# TarjetaModulo.net
KiCad netlist of a schematic drawn in Altium Designer
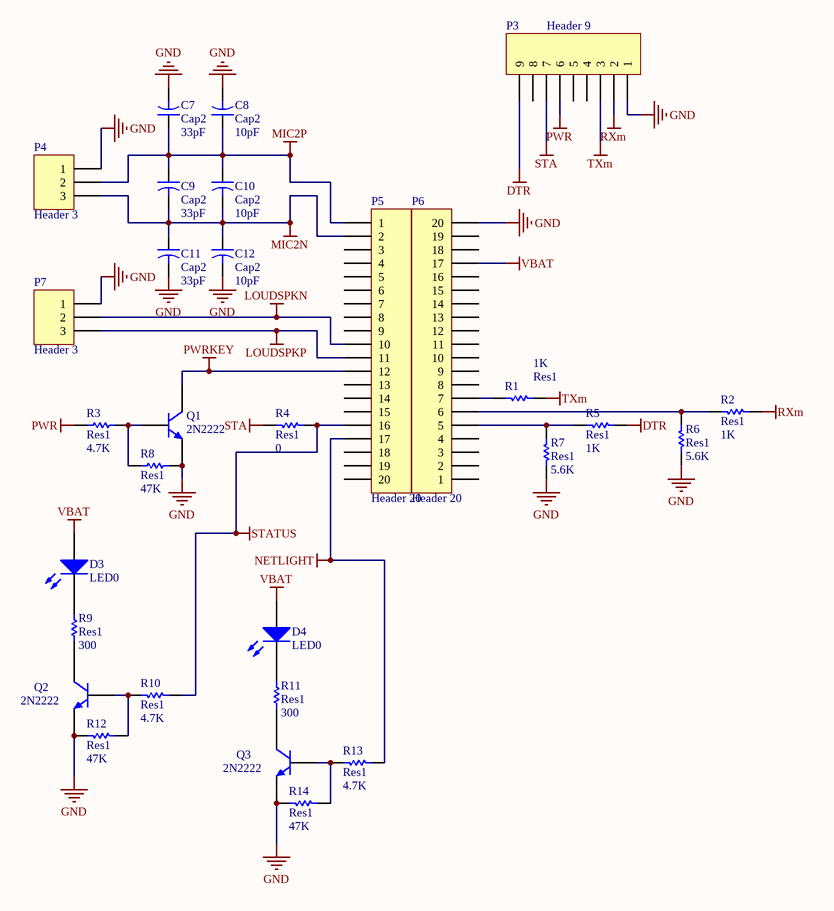
[diagram p0: TarjetaModulo.SchDoc]

(export (version "E")
  (design (tool "Eeschema 10.0.6"))
  (components
    (comp (ref "C7")
      (value "Cap2")
      (footprint "CAPR5-4X5")
      (description "Capacitor")
      (fields (field (name "ALTIUM_VALUE") "33pF") (field (name "PUBLISHER") "Altium Limited"))
      (libsource (lib "Miscellaneous Devices") (part "Cap2"))
    )
    (comp (ref "C8")
      (value "Cap2")
      (footprint "CAPR5-4X5")
      (description "Capacitor")
      (fields (field (name "ALTIUM_VALUE") "10pF") (field (name "PUBLISHER") "Altium Limited"))
      (libsource (lib "Miscellaneous Devices") (part "Cap2"))
    )
    (comp (ref "C9")
      (value "Cap2")
      (footprint "CAPR5-4X5")
      (description "Capacitor")
      (fields (field (name "ALTIUM_VALUE") "33pF") (field (name "PUBLISHER") "Altium Limited"))
      (libsource (lib "Miscellaneous Devices") (part "Cap2"))
    )
    (comp (ref "C10")
      (value "Cap2")
      (footprint "CAPR5-4X5")
      (description "Capacitor")
      (fields (field (name "ALTIUM_VALUE") "10pF") (field (name "PUBLISHER") "Altium Limited"))
      (libsource (lib "Miscellaneous Devices") (part "Cap2"))
    )
    (comp (ref "C11")
      (value "Cap2")
      (footprint "CAPR5-4X5")
      (description "Capacitor")
      (fields (field (name "ALTIUM_VALUE") "33pF") (field (name "PUBLISHER") "Altium Limited"))
      (libsource (lib "Miscellaneous Devices") (part "Cap2"))
    )
    (comp (ref "C12")
      (value "Cap2")
      (footprint "CAPR5-4X5")
      (description "Capacitor")
      (fields (field (name "ALTIUM_VALUE") "10pF") (field (name "PUBLISHER") "Altium Limited"))
      (libsource (lib "Miscellaneous Devices") (part "Cap2"))
    )
    (comp (ref "D3")
      (value "LED0")
      (footprint "LED-0")
      (description "Typical INFRARED GaAs LED")
      (fields (field (name "PUBLISHER") "Altium Limited"))
      (libsource (lib "Miscellaneous Devices") (part "LED0"))
    )
    (comp (ref "D4")
      (value "LED0")
      (footprint "LED-0")
      (description "Typical INFRARED GaAs LED")
      (fields (field (name "PUBLISHER") "Altium Limited"))
      (libsource (lib "Miscellaneous Devices") (part "LED0"))
    )
    (comp (ref "P3")
      (value "Header 9")
      (footprint "HDR1X9")
      (description "Header, 9-Pin")
      (fields (field (name "PUBLISHER") "Altium Limited"))
      (libsource (lib "Miscellaneous Connectors") (part "Header 9"))
    )
    (comp (ref "P4")
      (value "Header 3")
      (footprint "HDR1X3")
      (description "Header, 3-Pin")
      (fields (field (name "PUBLISHER") "Altium Limited"))
      (libsource (lib "Miscellaneous Connectors") (part "Header 3"))
    )
    (comp (ref "P5")
      (value "Header 20")
      (footprint "HDR1X20")
      (description "Header, 20-Pin")
      (fields (field (name "PUBLISHER") "Altium Limited"))
      (libsource (lib "") (part "Header 20_1"))
    )
    (comp (ref "P6")
      (value "Header 20")
      (footprint "HDR1X20")
      (description "Header, 20-Pin")
      (fields (field (name "PUBLISHER") "Altium Limited"))
      (libsource (lib "Miscellaneous Connectors") (part "Header 20"))
    )
    (comp (ref "P7")
      (value "Header 3")
      (footprint "HDR1X3")
      (description "Header, 3-Pin")
      (fields (field (name "PUBLISHER") "Altium Limited"))
      (libsource (lib "Miscellaneous Connectors") (part "Header 3"))
    )
    (comp (ref "Q1")
      (value "2N2222")
      (footprint "TO-92A")
      (description "NPN General Purpose Amplifier")
      (fields (field (name "PUBLISHER") "Altium Limited"))
      (libsource (lib "Miscellaneous Devices") (part "2N3904"))
    )
    (comp (ref "Q2")
      (value "2N2222")
      (footprint "TO-92A")
      (description "NPN General Purpose Amplifier")
      (fields (field (name "PUBLISHER") "Altium Limited"))
      (libsource (lib "Miscellaneous Devices") (part "2N3904"))
    )
    (comp (ref "Q3")
      (value "2N2222")
      (footprint "TO-92A")
      (description "NPN General Purpose Amplifier")
      (fields (field (name "PUBLISHER") "Altium Limited"))
      (libsource (lib "Miscellaneous Devices") (part "2N3904"))
    )
    (comp (ref "R1")
      (value "Res1")
      (footprint "AXIAL-0.3")
      (description "Resistor")
      (fields (field (name "ALTIUM_VALUE") "1K") (field (name "PUBLISHER") "Altium Limited"))
      (libsource (lib "Miscellaneous Devices") (part "Res1"))
    )
    (comp (ref "R2")
      (value "Res1")
      (footprint "AXIAL-0.3")
      (description "Resistor")
      (fields (field (name "ALTIUM_VALUE") "1K") (field (name "PUBLISHER") "Altium Limited"))
      (libsource (lib "Miscellaneous Devices") (part "Res1"))
    )
    (comp (ref "R3")
      (value "Res1")
      (footprint "AXIAL-0.3")
      (description "Resistor")
      (fields (field (name "ALTIUM_VALUE") "4.7K") (field (name "PUBLISHER") "Altium Limited"))
      (libsource (lib "Miscellaneous Devices") (part "Res1"))
    )
    (comp (ref "R4")
      (value "Res1")
      (footprint "AXIAL-0.3")
      (description "Resistor")
      (fields (field (name "ALTIUM_VALUE") "0") (field (name "PUBLISHER") "Altium Limited"))
      (libsource (lib "Miscellaneous Devices") (part "Res1"))
    )
    (comp (ref "R5")
      (value "Res1")
      (footprint "AXIAL-0.3")
      (description "Resistor")
      (fields (field (name "ALTIUM_VALUE") "1K") (field (name "PUBLISHER") "Altium Limited"))
      (libsource (lib "Miscellaneous Devices") (part "Res1"))
    )
    (comp (ref "R6")
      (value "Res1")
      (footprint "AXIAL-0.3")
      (description "Resistor")
      (fields (field (name "ALTIUM_VALUE") "5.6K") (field (name "PUBLISHER") "Altium Limited"))
      (libsource (lib "Miscellaneous Devices") (part "Res1"))
    )
    (comp (ref "R7")
      (value "Res1")
      (footprint "AXIAL-0.3")
      (description "Resistor")
      (fields (field (name "ALTIUM_VALUE") "5.6K") (field (name "PUBLISHER") "Altium Limited"))
      (libsource (lib "Miscellaneous Devices") (part "Res1"))
    )
    (comp (ref "R8")
      (value "Res1")
      (footprint "AXIAL-0.3")
      (description "Resistor")
      (fields (field (name "ALTIUM_VALUE") "47K") (field (name "PUBLISHER") "Altium Limited"))
      (libsource (lib "Miscellaneous Devices") (part "Res1"))
    )
    (comp (ref "R9")
      (value "Res1")
      (footprint "AXIAL-0.3")
      (description "Resistor")
      (fields (field (name "ALTIUM_VALUE") "300") (field (name "PUBLISHER") "Altium Limited"))
      (libsource (lib "Miscellaneous Devices") (part "Res1"))
    )
    (comp (ref "R10")
      (value "Res1")
      (footprint "AXIAL-0.3")
      (description "Resistor")
      (fields (field (name "ALTIUM_VALUE") "4.7K") (field (name "PUBLISHER") "Altium Limited"))
      (libsource (lib "Miscellaneous Devices") (part "Res1"))
    )
    (comp (ref "R11")
      (value "Res1")
      (footprint "AXIAL-0.3")
      (description "Resistor")
      (fields (field (name "ALTIUM_VALUE") "300") (field (name "PUBLISHER") "Altium Limited"))
      (libsource (lib "Miscellaneous Devices") (part "Res1"))
    )
    (comp (ref "R12")
      (value "Res1")
      (footprint "AXIAL-0.3")
      (description "Resistor")
      (fields (field (name "ALTIUM_VALUE") "47K") (field (name "PUBLISHER") "Altium Limited"))
      (libsource (lib "Miscellaneous Devices") (part "Res1"))
    )
    (comp (ref "R13")
      (value "Res1")
      (footprint "AXIAL-0.3")
      (description "Resistor")
      (fields (field (name "ALTIUM_VALUE") "4.7K") (field (name "PUBLISHER") "Altium Limited"))
      (libsource (lib "Miscellaneous Devices") (part "Res1"))
    )
    (comp (ref "R14")
      (value "Res1")
      (footprint "AXIAL-0.3")
      (description "Resistor")
      (fields (field (name "ALTIUM_VALUE") "47K") (field (name "PUBLISHER") "Altium Limited"))
      (libsource (lib "Miscellaneous Devices") (part "Res1"))
    )
  )
  (nets
    (net (code "1") (name "DTR") (class "Default")
      (node (ref "P3") (pin "9") (pinfunction "9_9") (pintype "passive"))
      (node (ref "R5") (pin "1") (pinfunction "1_1") (pintype "passive"))
    )
    (net (code "2") (name "GND") (class "Default")
      (node (ref "C11") (pin "2") (pinfunction "2_2") (pintype "passive"))
      (node (ref "C12") (pin "2") (pinfunction "2_2") (pintype "passive"))
      (node (ref "C7") (pin "2") (pinfunction "2_2") (pintype "passive"))
      (node (ref "C8") (pin "2") (pinfunction "2_2") (pintype "passive"))
      (node (ref "P3") (pin "1") (pinfunction "1_1") (pintype "passive"))
      (node (ref "P4") (pin "1") (pinfunction "1_1") (pintype "passive"))
      (node (ref "P6") (pin "20") (pinfunction "20_20") (pintype "passive"))
      (node (ref "P7") (pin "1") (pinfunction "1_1") (pintype "passive"))
      (node (ref "Q1") (pin "1") (pinfunction "E_1") (pintype "passive"))
      (node (ref "Q2") (pin "1") (pinfunction "E_1") (pintype "passive"))
      (node (ref "Q3") (pin "1") (pinfunction "E_1") (pintype "passive"))
      (node (ref "R12") (pin "2") (pinfunction "2_2") (pintype "passive"))
      (node (ref "R14") (pin "2") (pinfunction "2_2") (pintype "passive"))
      (node (ref "R6") (pin "2") (pinfunction "2_2") (pintype "passive"))
      (node (ref "R7") (pin "2") (pinfunction "2_2") (pintype "passive"))
      (node (ref "R8") (pin "2") (pinfunction "2_2") (pintype "passive"))
    )
    (net (code "3") (name "LOUDSPKN") (class "Default")
      (node (ref "P5") (pin "10") (pinfunction "10_10") (pintype "passive"))
      (node (ref "P7") (pin "2") (pinfunction "2_2") (pintype "passive"))
    )
    (net (code "4") (name "LOUDSPKP") (class "Default")
      (node (ref "P5") (pin "11") (pinfunction "11_11") (pintype "passive"))
      (node (ref "P7") (pin "3") (pinfunction "3_3") (pintype "passive"))
    )
    (net (code "5") (name "MIC2N") (class "Default")
      (node (ref "C10") (pin "2") (pinfunction "2_2") (pintype "passive"))
      (node (ref "C11") (pin "1") (pinfunction "1_1") (pintype "passive"))
      (node (ref "C12") (pin "1") (pinfunction "1_1") (pintype "passive"))
      (node (ref "C9") (pin "2") (pinfunction "2_2") (pintype "passive"))
      (node (ref "P4") (pin "3") (pinfunction "3_3") (pintype "passive"))
      (node (ref "P5") (pin "2") (pinfunction "2_2") (pintype "passive"))
    )
    (net (code "6") (name "MIC2P") (class "Default")
      (node (ref "C10") (pin "1") (pinfunction "1_1") (pintype "passive"))
      (node (ref "C7") (pin "1") (pinfunction "1_1") (pintype "passive"))
      (node (ref "C8") (pin "1") (pinfunction "1_1") (pintype "passive"))
      (node (ref "C9") (pin "1") (pinfunction "1_1") (pintype "passive"))
      (node (ref "P4") (pin "2") (pinfunction "2_2") (pintype "passive"))
      (node (ref "P5") (pin "1") (pinfunction "1_1") (pintype "passive"))
    )
    (net (code "7") (name "NETLIGHT") (class "Default")
      (node (ref "P5") (pin "17") (pinfunction "17_17") (pintype "passive"))
      (node (ref "R13") (pin "1") (pinfunction "1_1") (pintype "passive"))
    )
    (net (code "8") (name "Net-(D3-K)") (class "Default")
      (node (ref "D3") (pin "2") (pinfunction "K_2") (pintype "passive"))
      (node (ref "R9") (pin "2") (pinfunction "2_2") (pintype "passive"))
    )
    (net (code "9") (name "Net-(D4-K)") (class "Default")
      (node (ref "D4") (pin "2") (pinfunction "K_2") (pintype "passive"))
      (node (ref "R11") (pin "2") (pinfunction "2_2") (pintype "passive"))
    )
    (net (code "10") (name "Net-(P6-Pad5)") (class "Default")
      (node (ref "P6") (pin "5") (pinfunction "5_5") (pintype "passive"))
      (node (ref "R5") (pin "2") (pinfunction "2_2") (pintype "passive"))
      (node (ref "R7") (pin "1") (pinfunction "1_1") (pintype "passive"))
    )
    (net (code "11") (name "Net-(P6-Pad6)") (class "Default")
      (node (ref "P6") (pin "6") (pinfunction "6_6") (pintype "passive"))
      (node (ref "R2") (pin "2") (pinfunction "2_2") (pintype "passive"))
      (node (ref "R6") (pin "1") (pinfunction "1_1") (pintype "passive"))
    )
    (net (code "12") (name "Net-(P6-Pad7)") (class "Default")
      (node (ref "P6") (pin "7") (pinfunction "7_7") (pintype "passive"))
      (node (ref "R1") (pin "2") (pinfunction "2_2") (pintype "passive"))
    )
    (net (code "13") (name "Net-(Q1-B)") (class "Default")
      (node (ref "Q1") (pin "2") (pinfunction "B_2") (pintype "passive"))
      (node (ref "R3") (pin "2") (pinfunction "2_2") (pintype "passive"))
      (node (ref "R8") (pin "1") (pinfunction "1_1") (pintype "passive"))
    )
    (net (code "14") (name "Net-(Q2-B)") (class "Default")
      (node (ref "Q2") (pin "2") (pinfunction "B_2") (pintype "passive"))
      (node (ref "R10") (pin "2") (pinfunction "2_2") (pintype "passive"))
      (node (ref "R12") (pin "1") (pinfunction "1_1") (pintype "passive"))
    )
    (net (code "15") (name "Net-(Q2-C)") (class "Default")
      (node (ref "Q2") (pin "3") (pinfunction "C_3") (pintype "passive"))
      (node (ref "R9") (pin "1") (pinfunction "1_1") (pintype "passive"))
    )
    (net (code "16") (name "Net-(Q3-B)") (class "Default")
      (node (ref "Q3") (pin "2") (pinfunction "B_2") (pintype "passive"))
      (node (ref "R13") (pin "2") (pinfunction "2_2") (pintype "passive"))
      (node (ref "R14") (pin "1") (pinfunction "1_1") (pintype "passive"))
    )
    (net (code "17") (name "Net-(Q3-C)") (class "Default")
      (node (ref "Q3") (pin "3") (pinfunction "C_3") (pintype "passive"))
      (node (ref "R11") (pin "1") (pinfunction "1_1") (pintype "passive"))
    )
    (net (code "18") (name "PWR") (class "Default")
      (node (ref "P3") (pin "6") (pinfunction "6_6") (pintype "passive"))
      (node (ref "R3") (pin "1") (pinfunction "1_1") (pintype "passive"))
    )
    (net (code "19") (name "PWRKEY") (class "Default")
      (node (ref "P5") (pin "12") (pinfunction "12_12") (pintype "passive"))
      (node (ref "Q1") (pin "3") (pinfunction "C_3") (pintype "passive"))
    )
    (net (code "20") (name "RXm") (class "Default")
      (node (ref "P3") (pin "2") (pinfunction "2_2") (pintype "passive"))
      (node (ref "R2") (pin "1") (pinfunction "1_1") (pintype "passive"))
    )
    (net (code "21") (name "STA") (class "Default")
      (node (ref "P3") (pin "7") (pinfunction "7_7") (pintype "passive"))
      (node (ref "R4") (pin "2") (pinfunction "2_2") (pintype "passive"))
    )
    (net (code "22") (name "STATUS") (class "Default")
      (node (ref "P5") (pin "16") (pinfunction "16_16") (pintype "passive"))
      (node (ref "R10") (pin "1") (pinfunction "1_1") (pintype "passive"))
      (node (ref "R4") (pin "1") (pinfunction "1_1") (pintype "passive"))
    )
    (net (code "23") (name "TXm") (class "Default")
      (node (ref "P3") (pin "3") (pinfunction "3_3") (pintype "passive"))
      (node (ref "R1") (pin "1") (pinfunction "1_1") (pintype "passive"))
    )
    (net (code "24") (name "VBAT") (class "Default")
      (node (ref "D3") (pin "1") (pinfunction "A_1") (pintype "passive"))
      (node (ref "D4") (pin "1") (pinfunction "A_1") (pintype "passive"))
      (node (ref "P6") (pin "17") (pinfunction "17_17") (pintype "passive"))
    )
    (net (code "25") (name "unconnected-(P3-Pad4)") (class "Default")
      (node (ref "P3") (pin "4") (pinfunction "4_4") (pintype "passive"))
    )
    (net (code "26") (name "unconnected-(P3-Pad5)") (class "Default")
      (node (ref "P3") (pin "5") (pinfunction "5_5") (pintype "passive"))
    )
    (net (code "27") (name "unconnected-(P3-Pad8)") (class "Default")
      (node (ref "P3") (pin "8") (pinfunction "8_8") (pintype "passive"))
    )
    (net (code "28") (name "unconnected-(P5-Pad3)") (class "Default")
      (node (ref "P5") (pin "3") (pinfunction "3_3") (pintype "passive"))
    )
    (net (code "29") (name "unconnected-(P5-Pad4)") (class "Default")
      (node (ref "P5") (pin "4") (pinfunction "4_4") (pintype "passive"))
    )
    (net (code "30") (name "unconnected-(P5-Pad5)") (class "Default")
      (node (ref "P5") (pin "5") (pinfunction "5_5") (pintype "passive"))
    )
    (net (code "31") (name "unconnected-(P5-Pad6)") (class "Default")
      (node (ref "P5") (pin "6") (pinfunction "6_6") (pintype "passive"))
    )
    (net (code "32") (name "unconnected-(P5-Pad7)") (class "Default")
      (node (ref "P5") (pin "7") (pinfunction "7_7") (pintype "passive"))
    )
    (net (code "33") (name "unconnected-(P5-Pad8)") (class "Default")
      (node (ref "P5") (pin "8") (pinfunction "8_8") (pintype "passive"))
    )
    (net (code "34") (name "unconnected-(P5-Pad9)") (class "Default")
      (node (ref "P5") (pin "9") (pinfunction "9_9") (pintype "passive"))
    )
    (net (code "35") (name "unconnected-(P5-Pad13)") (class "Default")
      (node (ref "P5") (pin "13") (pinfunction "13_13") (pintype "passive"))
    )
    (net (code "36") (name "unconnected-(P5-Pad14)") (class "Default")
      (node (ref "P5") (pin "14") (pinfunction "14_14") (pintype "passive"))
    )
    (net (code "37") (name "unconnected-(P5-Pad15)") (class "Default")
      (node (ref "P5") (pin "15") (pinfunction "15_15") (pintype "passive"))
    )
    (net (code "38") (name "unconnected-(P5-Pad18)") (class "Default")
      (node (ref "P5") (pin "18") (pinfunction "18_18") (pintype "passive"))
    )
    (net (code "39") (name "unconnected-(P5-Pad19)") (class "Default")
      (node (ref "P5") (pin "19") (pinfunction "19_19") (pintype "passive"))
    )
    (net (code "40") (name "unconnected-(P5-Pad20)") (class "Default")
      (node (ref "P5") (pin "20") (pinfunction "20_20") (pintype "passive"))
    )
    (net (code "41") (name "unconnected-(P6-Pad1)") (class "Default")
      (node (ref "P6") (pin "1") (pinfunction "1_1") (pintype "passive"))
    )
    (net (code "42") (name "unconnected-(P6-Pad2)") (class "Default")
      (node (ref "P6") (pin "2") (pinfunction "2_2") (pintype "passive"))
    )
    (net (code "43") (name "unconnected-(P6-Pad3)") (class "Default")
      (node (ref "P6") (pin "3") (pinfunction "3_3") (pintype "passive"))
    )
    (net (code "44") (name "unconnected-(P6-Pad4)") (class "Default")
      (node (ref "P6") (pin "4") (pinfunction "4_4") (pintype "passive"))
    )
    (net (code "45") (name "unconnected-(P6-Pad8)") (class "Default")
      (node (ref "P6") (pin "8") (pinfunction "8_8") (pintype "passive"))
    )
    (net (code "46") (name "unconnected-(P6-Pad9)") (class "Default")
      (node (ref "P6") (pin "9") (pinfunction "9_9") (pintype "passive"))
    )
    (net (code "47") (name "unconnected-(P6-Pad10)") (class "Default")
      (node (ref "P6") (pin "10") (pinfunction "10_10") (pintype "passive"))
    )
    (net (code "48") (name "unconnected-(P6-Pad11)") (class "Default")
      (node (ref "P6") (pin "11") (pinfunction "11_11") (pintype "passive"))
    )
    (net (code "49") (name "unconnected-(P6-Pad12)") (class "Default")
      (node (ref "P6") (pin "12") (pinfunction "12_12") (pintype "passive"))
    )
    (net (code "50") (name "unconnected-(P6-Pad13)") (class "Default")
      (node (ref "P6") (pin "13") (pinfunction "13_13") (pintype "passive"))
    )
    (net (code "51") (name "unconnected-(P6-Pad14)") (class "Default")
      (node (ref "P6") (pin "14") (pinfunction "14_14") (pintype "passive"))
    )
    (net (code "52") (name "unconnected-(P6-Pad15)") (class "Default")
      (node (ref "P6") (pin "15") (pinfunction "15_15") (pintype "passive"))
    )
    (net (code "53") (name "unconnected-(P6-Pad16)") (class "Default")
      (node (ref "P6") (pin "16") (pinfunction "16_16") (pintype "passive"))
    )
    (net (code "54") (name "unconnected-(P6-Pad18)") (class "Default")
      (node (ref "P6") (pin "18") (pinfunction "18_18") (pintype "passive"))
    )
    (net (code "55") (name "unconnected-(P6-Pad19)") (class "Default")
      (node (ref "P6") (pin "19") (pinfunction "19_19") (pintype "passive"))
    )
  )
)
